# ZigUP.net
KiCad netlist of a schematic drawn in EAGLE
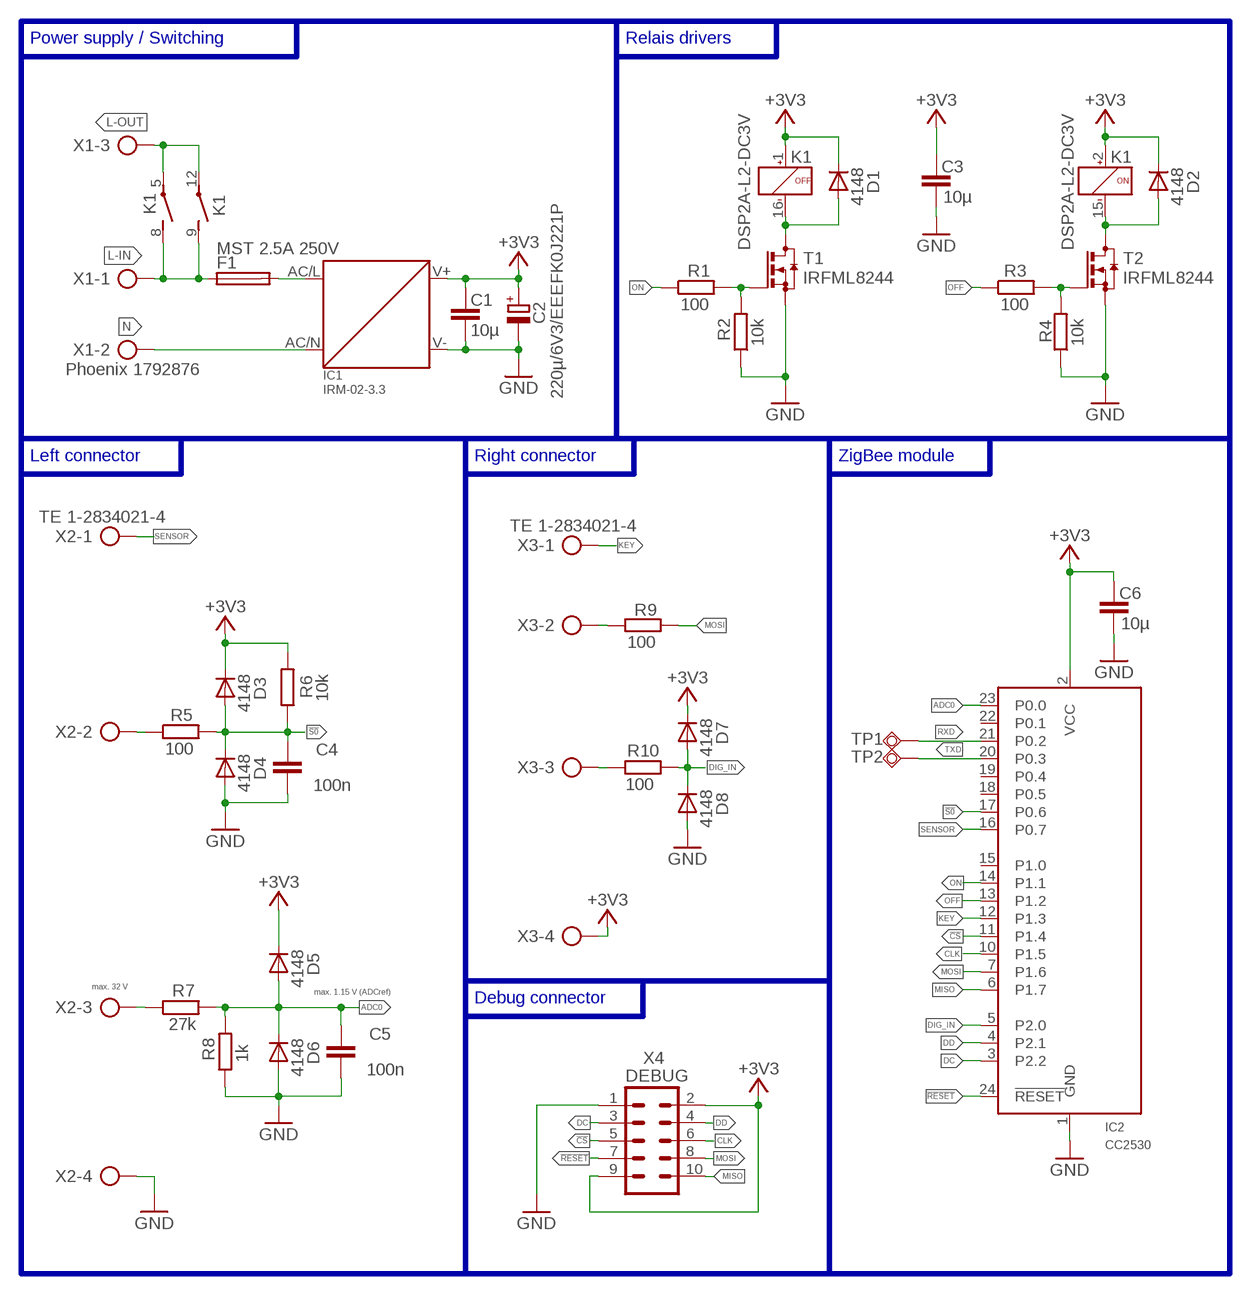
[diagram p0: schematic, sheet 1]

(export (version "E")
  (design (tool "Eeschema 10.0.6"))
  (components
    (comp (ref "C1")
      (value "10µ")
      (footprint "eagle-import:C0805")
      (libsource (lib "eagle-import") (part "C-EUC0805"))
    )
    (comp (ref "C2")
      (value "220µ/6V3/EEEFK0J221P")
      (footprint "eagle-import:PANASONIC_D")
      (libsource (lib "eagle-import") (part "CPOL-EUD"))
    )
    (comp (ref "C3")
      (value "10µ")
      (footprint "eagle-import:C0805")
      (libsource (lib "eagle-import") (part "C-EUC0805"))
    )
    (comp (ref "C4")
      (value "100n")
      (footprint "eagle-import:C0805")
      (libsource (lib "eagle-import") (part "C-EUC0805"))
    )
    (comp (ref "C5")
      (value "100n")
      (footprint "eagle-import:C0805")
      (libsource (lib "eagle-import") (part "C-EUC0805"))
    )
    (comp (ref "C6")
      (value "10µ")
      (footprint "eagle-import:C0805")
      (libsource (lib "eagle-import") (part "C-EUC0805"))
    )
    (comp (ref "D1")
      (value "4148")
      (footprint "eagle-import:1206")
      (libsource (lib "eagle-import") (part "TS4148"))
    )
    (comp (ref "D2")
      (value "4148")
      (footprint "eagle-import:1206")
      (libsource (lib "eagle-import") (part "TS4148"))
    )
    (comp (ref "D3")
      (value "4148")
      (footprint "eagle-import:1206")
      (libsource (lib "eagle-import") (part "TS4148"))
    )
    (comp (ref "D4")
      (value "4148")
      (footprint "eagle-import:1206")
      (libsource (lib "eagle-import") (part "TS4148"))
    )
    (comp (ref "D5")
      (value "4148")
      (footprint "eagle-import:1206")
      (libsource (lib "eagle-import") (part "TS4148"))
    )
    (comp (ref "D6")
      (value "4148")
      (footprint "eagle-import:1206")
      (libsource (lib "eagle-import") (part "TS4148"))
    )
    (comp (ref "D7")
      (value "4148")
      (footprint "eagle-import:1206")
      (libsource (lib "eagle-import") (part "TS4148"))
    )
    (comp (ref "D8")
      (value "4148")
      (footprint "eagle-import:1206")
      (libsource (lib "eagle-import") (part "TS4148"))
    )
    (comp (ref "F1")
      (value "MST 2.5A 250V")
      (footprint "eagle-import:MST")
      (libsource (lib "eagle-import") (part "MST"))
    )
    (comp (ref "IC1")
      (value "IRM-02-3.3")
      (footprint "eagle-import:IRM-01")
      (libsource (lib "eagle-import") (part "IRM-01"))
    )
    (comp (ref "IC2")
      (value "CC2530")
      (footprint "eagle-import:E18-MS1-PCB")
      (libsource (lib "eagle-import") (part "CC2530THT"))
    )
    (comp (ref "K1")
      (value "DSP2A-L2-DC3V")
      (footprint "eagle-import:DSP2A-L2")
      (libsource (lib "eagle-import") (part "DSP2A-L2"))
    )
    (comp (ref "R1")
      (value "100")
      (footprint "eagle-import:R0805")
      (libsource (lib "eagle-import") (part "R-EU_R0805"))
    )
    (comp (ref "R2")
      (value "10k")
      (footprint "eagle-import:R0805")
      (libsource (lib "eagle-import") (part "R-EU_R0805"))
    )
    (comp (ref "R3")
      (value "100")
      (footprint "eagle-import:R0805")
      (libsource (lib "eagle-import") (part "R-EU_R0805"))
    )
    (comp (ref "R4")
      (value "10k")
      (footprint "eagle-import:R0805")
      (libsource (lib "eagle-import") (part "R-EU_R0805"))
    )
    (comp (ref "R5")
      (value "100")
      (footprint "eagle-import:R0805")
      (libsource (lib "eagle-import") (part "R-EU_R0805"))
    )
    (comp (ref "R6")
      (value "10k")
      (footprint "eagle-import:R0805")
      (libsource (lib "eagle-import") (part "R-EU_R0805"))
    )
    (comp (ref "R7")
      (value "27k")
      (footprint "eagle-import:R0805")
      (libsource (lib "eagle-import") (part "R-EU_R0805"))
    )
    (comp (ref "R8")
      (value "1k")
      (footprint "eagle-import:R0805")
      (libsource (lib "eagle-import") (part "R-EU_R0805"))
    )
    (comp (ref "R9")
      (value "100")
      (footprint "eagle-import:R0805")
      (libsource (lib "eagle-import") (part "R-EU_R0805"))
    )
    (comp (ref "R10")
      (value "100")
      (footprint "eagle-import:R0805")
      (libsource (lib "eagle-import") (part "R-EU_R0805"))
    )
    (comp (ref "T1")
      (value "IRFML8244")
      (footprint "eagle-import:SOT23")
      (libsource (lib "eagle-import") (part "BSS123"))
    )
    (comp (ref "T2")
      (value "IRFML8244")
      (footprint "eagle-import:SOT23")
      (libsource (lib "eagle-import") (part "BSS123"))
    )
    (comp (ref "TP1")
      (value "RX")
      (footprint "eagle-import:TP15SQ")
      (libsource (lib "eagle-import") (part "TPSQTP15SQ"))
    )
    (comp (ref "TP2")
      (value "TX")
      (footprint "eagle-import:TP15SQ")
      (libsource (lib "eagle-import") (part "TPSQTP15SQ"))
    )
    (comp (ref "X1")
      (value "Phoenix 1792876")
      (footprint "eagle-import:PTS-3")
      (libsource (lib "eagle-import") (part "PTS3"))
    )
    (comp (ref "X2")
      (value "TE 1-2834021-4")
      (footprint "eagle-import:MSC4")
      (libsource (lib "eagle-import") (part "MSC4"))
    )
    (comp (ref "X3")
      (value "TE 1-2834021-4")
      (footprint "eagle-import:MSC4")
      (libsource (lib "eagle-import") (part "MSC4"))
    )
    (comp (ref "X4")
      (value "DEBUG")
      (footprint "eagle-import:MA05-2")
      (libsource (lib "eagle-import") (part "MA05-2"))
    )
  )
  (nets
    (net (code "2") (name "+3V3") (class "Default")
      (node (ref "C1") (pin "1") (pinfunction "1_1") (pintype "passive"))
      (node (ref "C2") (pin "+") (pinfunction "+_+") (pintype "passive"))
      (node (ref "C3") (pin "1") (pinfunction "1_1") (pintype "passive"))
      (node (ref "C6") (pin "1") (pinfunction "1_1") (pintype "passive"))
      (node (ref "D1") (pin "K") (pinfunction "K_K") (pintype "passive"))
      (node (ref "D2") (pin "K") (pinfunction "K_K") (pintype "passive"))
      (node (ref "D3") (pin "K") (pinfunction "K_K") (pintype "passive"))
      (node (ref "D5") (pin "K") (pinfunction "K_K") (pintype "passive"))
      (node (ref "D7") (pin "K") (pinfunction "K_K") (pintype "passive"))
      (node (ref "IC1") (pin "V+") (pinfunction "V+_V+") (pintype "passive"))
      (node (ref "IC2") (pin "2") (pinfunction "VCC_2") (pintype "passive"))
      (node (ref "K1") (pin "1") (pinfunction "+_1") (pintype "passive"))
      (node (ref "K1") (pin "2") (pinfunction "+_2") (pintype "passive"))
      (node (ref "R6") (pin "2") (pinfunction "2_2") (pintype "passive"))
      (node (ref "X3") (pin "4") (pinfunction "KL_4") (pintype "passive"))
      (node (ref "X4") (pin "2") (pinfunction "2_2") (pintype "passive"))
      (node (ref "X4") (pin "9") (pinfunction "9_9") (pintype "passive"))
    )
    (net (code "4") (name "/~{CS}") (class "Default")
      (node (ref "IC2") (pin "11") (pinfunction "P1.4_11") (pintype "passive"))
      (node (ref "X4") (pin "5") (pinfunction "5_5") (pintype "passive"))
    )
    (net (code "5") (name "/~{RESET}") (class "Default")
      (node (ref "IC2") (pin "24") (pinfunction "~{RESET}_24") (pintype "passive"))
      (node (ref "X4") (pin "7") (pinfunction "7_7") (pintype "passive"))
    )
    (net (code "6") (name "/~{S0}") (class "Default")
      (node (ref "C4") (pin "1") (pinfunction "1_1") (pintype "passive"))
      (node (ref "D3") (pin "A") (pinfunction "A_A") (pintype "passive"))
      (node (ref "D4") (pin "K") (pinfunction "K_K") (pintype "passive"))
      (node (ref "IC2") (pin "17") (pinfunction "P0.6_17") (pintype "passive"))
      (node (ref "R5") (pin "2") (pinfunction "2_2") (pintype "passive"))
      (node (ref "R6") (pin "1") (pinfunction "1_1") (pintype "passive"))
    )
    (net (code "7") (name "ADC0") (class "Default")
      (node (ref "C5") (pin "1") (pinfunction "1_1") (pintype "passive"))
      (node (ref "D5") (pin "A") (pinfunction "A_A") (pintype "passive"))
      (node (ref "D6") (pin "K") (pinfunction "K_K") (pintype "passive"))
      (node (ref "IC2") (pin "23") (pinfunction "P0.0_23") (pintype "passive"))
      (node (ref "R7") (pin "2") (pinfunction "2_2") (pintype "passive"))
      (node (ref "R8") (pin "2") (pinfunction "2_2") (pintype "passive"))
    )
    (net (code "8") (name "CLK") (class "Default")
      (node (ref "IC2") (pin "10") (pinfunction "P1.5_10") (pintype "passive"))
      (node (ref "X4") (pin "6") (pinfunction "6_6") (pintype "passive"))
    )
    (net (code "9") (name "DC") (class "Default")
      (node (ref "IC2") (pin "3") (pinfunction "P2.2_3") (pintype "passive"))
      (node (ref "X4") (pin "3") (pinfunction "3_3") (pintype "passive"))
    )
    (net (code "10") (name "DD") (class "Default")
      (node (ref "IC2") (pin "4") (pinfunction "P2.1_4") (pintype "passive"))
      (node (ref "X4") (pin "4") (pinfunction "4_4") (pintype "passive"))
    )
    (net (code "11") (name "DIG_IN") (class "Default")
      (node (ref "D7") (pin "A") (pinfunction "A_A") (pintype "passive"))
      (node (ref "D8") (pin "K") (pinfunction "K_K") (pintype "passive"))
      (node (ref "IC2") (pin "5") (pinfunction "P2.0_5") (pintype "passive"))
      (node (ref "R10") (pin "2") (pinfunction "2_2") (pintype "passive"))
    )
    (net (code "12") (name "GND") (class "Default")
      (node (ref "C1") (pin "2") (pinfunction "2_2") (pintype "passive"))
      (node (ref "C2") (pin "-") (pinfunction "-_-") (pintype "passive"))
      (node (ref "C3") (pin "2") (pinfunction "2_2") (pintype "passive"))
      (node (ref "C4") (pin "2") (pinfunction "2_2") (pintype "passive"))
      (node (ref "C5") (pin "2") (pinfunction "2_2") (pintype "passive"))
      (node (ref "C6") (pin "2") (pinfunction "2_2") (pintype "passive"))
      (node (ref "D4") (pin "A") (pinfunction "A_A") (pintype "passive"))
      (node (ref "D6") (pin "A") (pinfunction "A_A") (pintype "passive"))
      (node (ref "D8") (pin "A") (pinfunction "A_A") (pintype "passive"))
      (node (ref "IC1") (pin "V-") (pinfunction "V-_V-") (pintype "passive"))
      (node (ref "IC2") (pin "1") (pinfunction "GND_1") (pintype "passive"))
      (node (ref "R2") (pin "1") (pinfunction "1_1") (pintype "passive"))
      (node (ref "R4") (pin "1") (pinfunction "1_1") (pintype "passive"))
      (node (ref "R8") (pin "1") (pinfunction "1_1") (pintype "passive"))
      (node (ref "T1") (pin "2") (pinfunction "S_2") (pintype "passive"))
      (node (ref "T2") (pin "2") (pinfunction "S_2") (pintype "passive"))
      (node (ref "X2") (pin "4") (pinfunction "KL_4") (pintype "passive"))
      (node (ref "X4") (pin "1") (pinfunction "1_1") (pintype "passive"))
    )
    (net (code "13") (name "KEY") (class "Default")
      (node (ref "IC2") (pin "12") (pinfunction "P1.3_12") (pintype "passive"))
      (node (ref "X3") (pin "1") (pinfunction "KL_1") (pintype "passive"))
    )
    (net (code "14") (name "L-IN") (class "Default")
      (node (ref "F1") (pin "1") (pinfunction "1_1") (pintype "passive"))
      (node (ref "K1") (pin "8") (pinfunction "C_8") (pintype "passive"))
      (node (ref "K1") (pin "9") (pinfunction "C_9") (pintype "passive"))
      (node (ref "X1") (pin "1") (pinfunction "KL_1") (pintype "passive"))
    )
    (net (code "15") (name "L-OUT") (class "Default")
      (node (ref "K1") (pin "12") (pinfunction "S_12") (pintype "passive"))
      (node (ref "K1") (pin "5") (pinfunction "S_5") (pintype "passive"))
      (node (ref "X1") (pin "3") (pinfunction "KL_3") (pintype "passive"))
    )
    (net (code "16") (name "MISO") (class "Default")
      (node (ref "IC2") (pin "6") (pinfunction "P1.7_6") (pintype "passive"))
      (node (ref "X4") (pin "10") (pinfunction "10_10") (pintype "passive"))
    )
    (net (code "17") (name "MOSI") (class "Default")
      (node (ref "IC2") (pin "7") (pinfunction "P1.6_7") (pintype "passive"))
      (node (ref "R9") (pin "1") (pinfunction "1_1") (pintype "passive"))
      (node (ref "X4") (pin "8") (pinfunction "8_8") (pintype "passive"))
    )
    (net (code "18") (name "N") (class "Default")
      (node (ref "IC1") (pin "AC/N") (pinfunction "AC/N_AC/N") (pintype "passive"))
      (node (ref "X1") (pin "2") (pinfunction "KL_2") (pintype "passive"))
    )
    (net (code "19") (name "Net-(F1-Pad2)") (class "Default")
      (node (ref "F1") (pin "2") (pinfunction "2_2") (pintype "passive"))
      (node (ref "IC1") (pin "AC/L") (pinfunction "AC/L_AC/L") (pintype "passive"))
    )
    (net (code "20") (name "Net-(K1A--)") (class "Default")
      (node (ref "D1") (pin "A") (pinfunction "A_A") (pintype "passive"))
      (node (ref "K1") (pin "16") (pinfunction "-_16") (pintype "passive"))
      (node (ref "T1") (pin "3") (pinfunction "D_3") (pintype "passive"))
    )
    (net (code "21") (name "Net-(K1B--)") (class "Default")
      (node (ref "D2") (pin "A") (pinfunction "A_A") (pintype "passive"))
      (node (ref "K1") (pin "15") (pinfunction "-_15") (pintype "passive"))
      (node (ref "T2") (pin "3") (pinfunction "D_3") (pintype "passive"))
    )
    (net (code "22") (name "Net-(T1-G)") (class "Default")
      (node (ref "R1") (pin "2") (pinfunction "2_2") (pintype "passive"))
      (node (ref "R2") (pin "2") (pinfunction "2_2") (pintype "passive"))
      (node (ref "T1") (pin "1") (pinfunction "G_1") (pintype "passive"))
    )
    (net (code "23") (name "Net-(T2-G)") (class "Default")
      (node (ref "R3") (pin "2") (pinfunction "2_2") (pintype "passive"))
      (node (ref "R4") (pin "2") (pinfunction "2_2") (pintype "passive"))
      (node (ref "T2") (pin "1") (pinfunction "G_1") (pintype "passive"))
    )
    (net (code "24") (name "Net-(X2B-KL)") (class "Default")
      (node (ref "R5") (pin "1") (pinfunction "1_1") (pintype "passive"))
      (node (ref "X2") (pin "2") (pinfunction "KL_2") (pintype "passive"))
    )
    (net (code "25") (name "Net-(X2C-KL)") (class "Default")
      (node (ref "R7") (pin "1") (pinfunction "1_1") (pintype "passive"))
      (node (ref "X2") (pin "3") (pinfunction "KL_3") (pintype "passive"))
    )
    (net (code "26") (name "Net-(X3B-KL)") (class "Default")
      (node (ref "R9") (pin "2") (pinfunction "2_2") (pintype "passive"))
      (node (ref "X3") (pin "2") (pinfunction "KL_2") (pintype "passive"))
    )
    (net (code "27") (name "Net-(X3C-KL)") (class "Default")
      (node (ref "R10") (pin "1") (pinfunction "1_1") (pintype "passive"))
      (node (ref "X3") (pin "3") (pinfunction "KL_3") (pintype "passive"))
    )
    (net (code "28") (name "OFF") (class "Default")
      (node (ref "IC2") (pin "13") (pinfunction "P1.2_13") (pintype "passive"))
      (node (ref "R3") (pin "1") (pinfunction "1_1") (pintype "passive"))
    )
    (net (code "29") (name "ON") (class "Default")
      (node (ref "IC2") (pin "14") (pinfunction "P1.1_14") (pintype "passive"))
      (node (ref "R1") (pin "1") (pinfunction "1_1") (pintype "passive"))
    )
    (net (code "30") (name "RXD") (class "Default")
      (node (ref "IC2") (pin "21") (pinfunction "P0.2_21") (pintype "passive"))
      (node (ref "TP1") (pin "TP") (pinfunction "TP_TP") (pintype "input"))
    )
    (net (code "31") (name "SENSOR") (class "Default")
      (node (ref "IC2") (pin "16") (pinfunction "P0.7_16") (pintype "passive"))
      (node (ref "X2") (pin "1") (pinfunction "KL_1") (pintype "passive"))
    )
    (net (code "32") (name "TXD") (class "Default")
      (node (ref "IC2") (pin "20") (pinfunction "P0.3_20") (pintype "passive"))
      (node (ref "TP2") (pin "TP") (pinfunction "TP_TP") (pintype "input"))
    )
    (net (code "33") (name "unconnected-(IC2-P0.1-Pad22)") (class "Default")
      (node (ref "IC2") (pin "22") (pinfunction "P0.1_22") (pintype "passive"))
    )
    (net (code "34") (name "unconnected-(IC2-P0.4-Pad19)") (class "Default")
      (node (ref "IC2") (pin "19") (pinfunction "P0.4_19") (pintype "passive"))
    )
    (net (code "35") (name "unconnected-(IC2-P0.5-Pad18)") (class "Default")
      (node (ref "IC2") (pin "18") (pinfunction "P0.5_18") (pintype "passive"))
    )
    (net (code "36") (name "unconnected-(IC2-P1.0-Pad15)") (class "Default")
      (node (ref "IC2") (pin "15") (pinfunction "P1.0_15") (pintype "passive"))
    )
  )
)
